# LedDriver.net
KiCad netlist of a schematic drawn in EAGLE
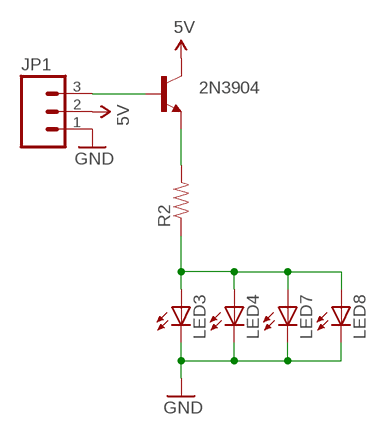
[diagram p0: schematic, sheet 1]

(export (version "E")
  (design (tool "Eeschema 10.0.6"))
  (components
    (comp (ref "2N3904")
      (value "TRANSISTOR_NPNTO-92-AMMO")
      (footprint "eagle-import:TO-92-AMMO")
      (libsource (lib "eagle-import") (part "TRANSISTOR_NPNTO-92-AMMO"))
    )
    (comp (ref "JP1")
      (value "M03PTH")
      (footprint "eagle-import:1X03")
      (libsource (lib "eagle-import") (part "M03PTH"))
    )
    (comp (ref "LED3")
      (value "LED5MM")
      (footprint "eagle-import:LED5MM")
      (libsource (lib "eagle-import") (part "LED5MM"))
    )
    (comp (ref "LED4")
      (value "LED5MM")
      (footprint "eagle-import:LED5MM")
      (libsource (lib "eagle-import") (part "LED5MM"))
    )
    (comp (ref "LED7")
      (value "LED5MM")
      (footprint "eagle-import:LED5MM")
      (libsource (lib "eagle-import") (part "LED5MM"))
    )
    (comp (ref "LED8")
      (value "LED5MM")
      (footprint "eagle-import:LED5MM")
      (libsource (lib "eagle-import") (part "LED5MM"))
    )
    (comp (ref "R2")
      (value "RESISTORAXIAL-0.3")
      (footprint "eagle-import:AXIAL-0.3")
      (libsource (lib "eagle-import") (part "RESISTORAXIAL-0.3"))
    )
  )
  (nets
    (net (code "1") (name "5V") (class "Default")
      (node (ref "2N3904") (pin "3") (pinfunction "C_3") (pintype "passive"))
      (node (ref "JP1") (pin "2") (pinfunction "2_2") (pintype "passive"))
    )
    (net (code "2") (name "GND") (class "Default")
      (node (ref "JP1") (pin "1") (pinfunction "1_1") (pintype "passive"))
      (node (ref "LED3") (pin "K") (pinfunction "C_K") (pintype "passive"))
      (node (ref "LED4") (pin "K") (pinfunction "C_K") (pintype "passive"))
      (node (ref "LED7") (pin "K") (pinfunction "C_K") (pintype "passive"))
      (node (ref "LED8") (pin "K") (pinfunction "C_K") (pintype "passive"))
    )
    (net (code "3") (name "Net-(2N3904-B)") (class "Default")
      (node (ref "2N3904") (pin "2") (pinfunction "B_2") (pintype "passive"))
      (node (ref "JP1") (pin "3") (pinfunction "3_3") (pintype "passive"))
    )
    (net (code "4") (name "Net-(2N3904-E)") (class "Default")
      (node (ref "2N3904") (pin "1") (pinfunction "E_1") (pintype "passive"))
      (node (ref "R2") (pin "P$2") (pinfunction "2_P$2") (pintype "passive"))
    )
    (net (code "5") (name "Net-(R2-1)") (class "Default")
      (node (ref "LED3") (pin "A") (pinfunction "A_A") (pintype "passive"))
      (node (ref "LED4") (pin "A") (pinfunction "A_A") (pintype "passive"))
      (node (ref "LED7") (pin "A") (pinfunction "A_A") (pintype "passive"))
      (node (ref "LED8") (pin "A") (pinfunction "A_A") (pintype "passive"))
      (node (ref "R2") (pin "P$1") (pinfunction "1_P$1") (pintype "passive"))
    )
  )
)
